# CLIPPER_CLAMPER_PCB.net
KiCad netlist of a schematic drawn in EasyEDA
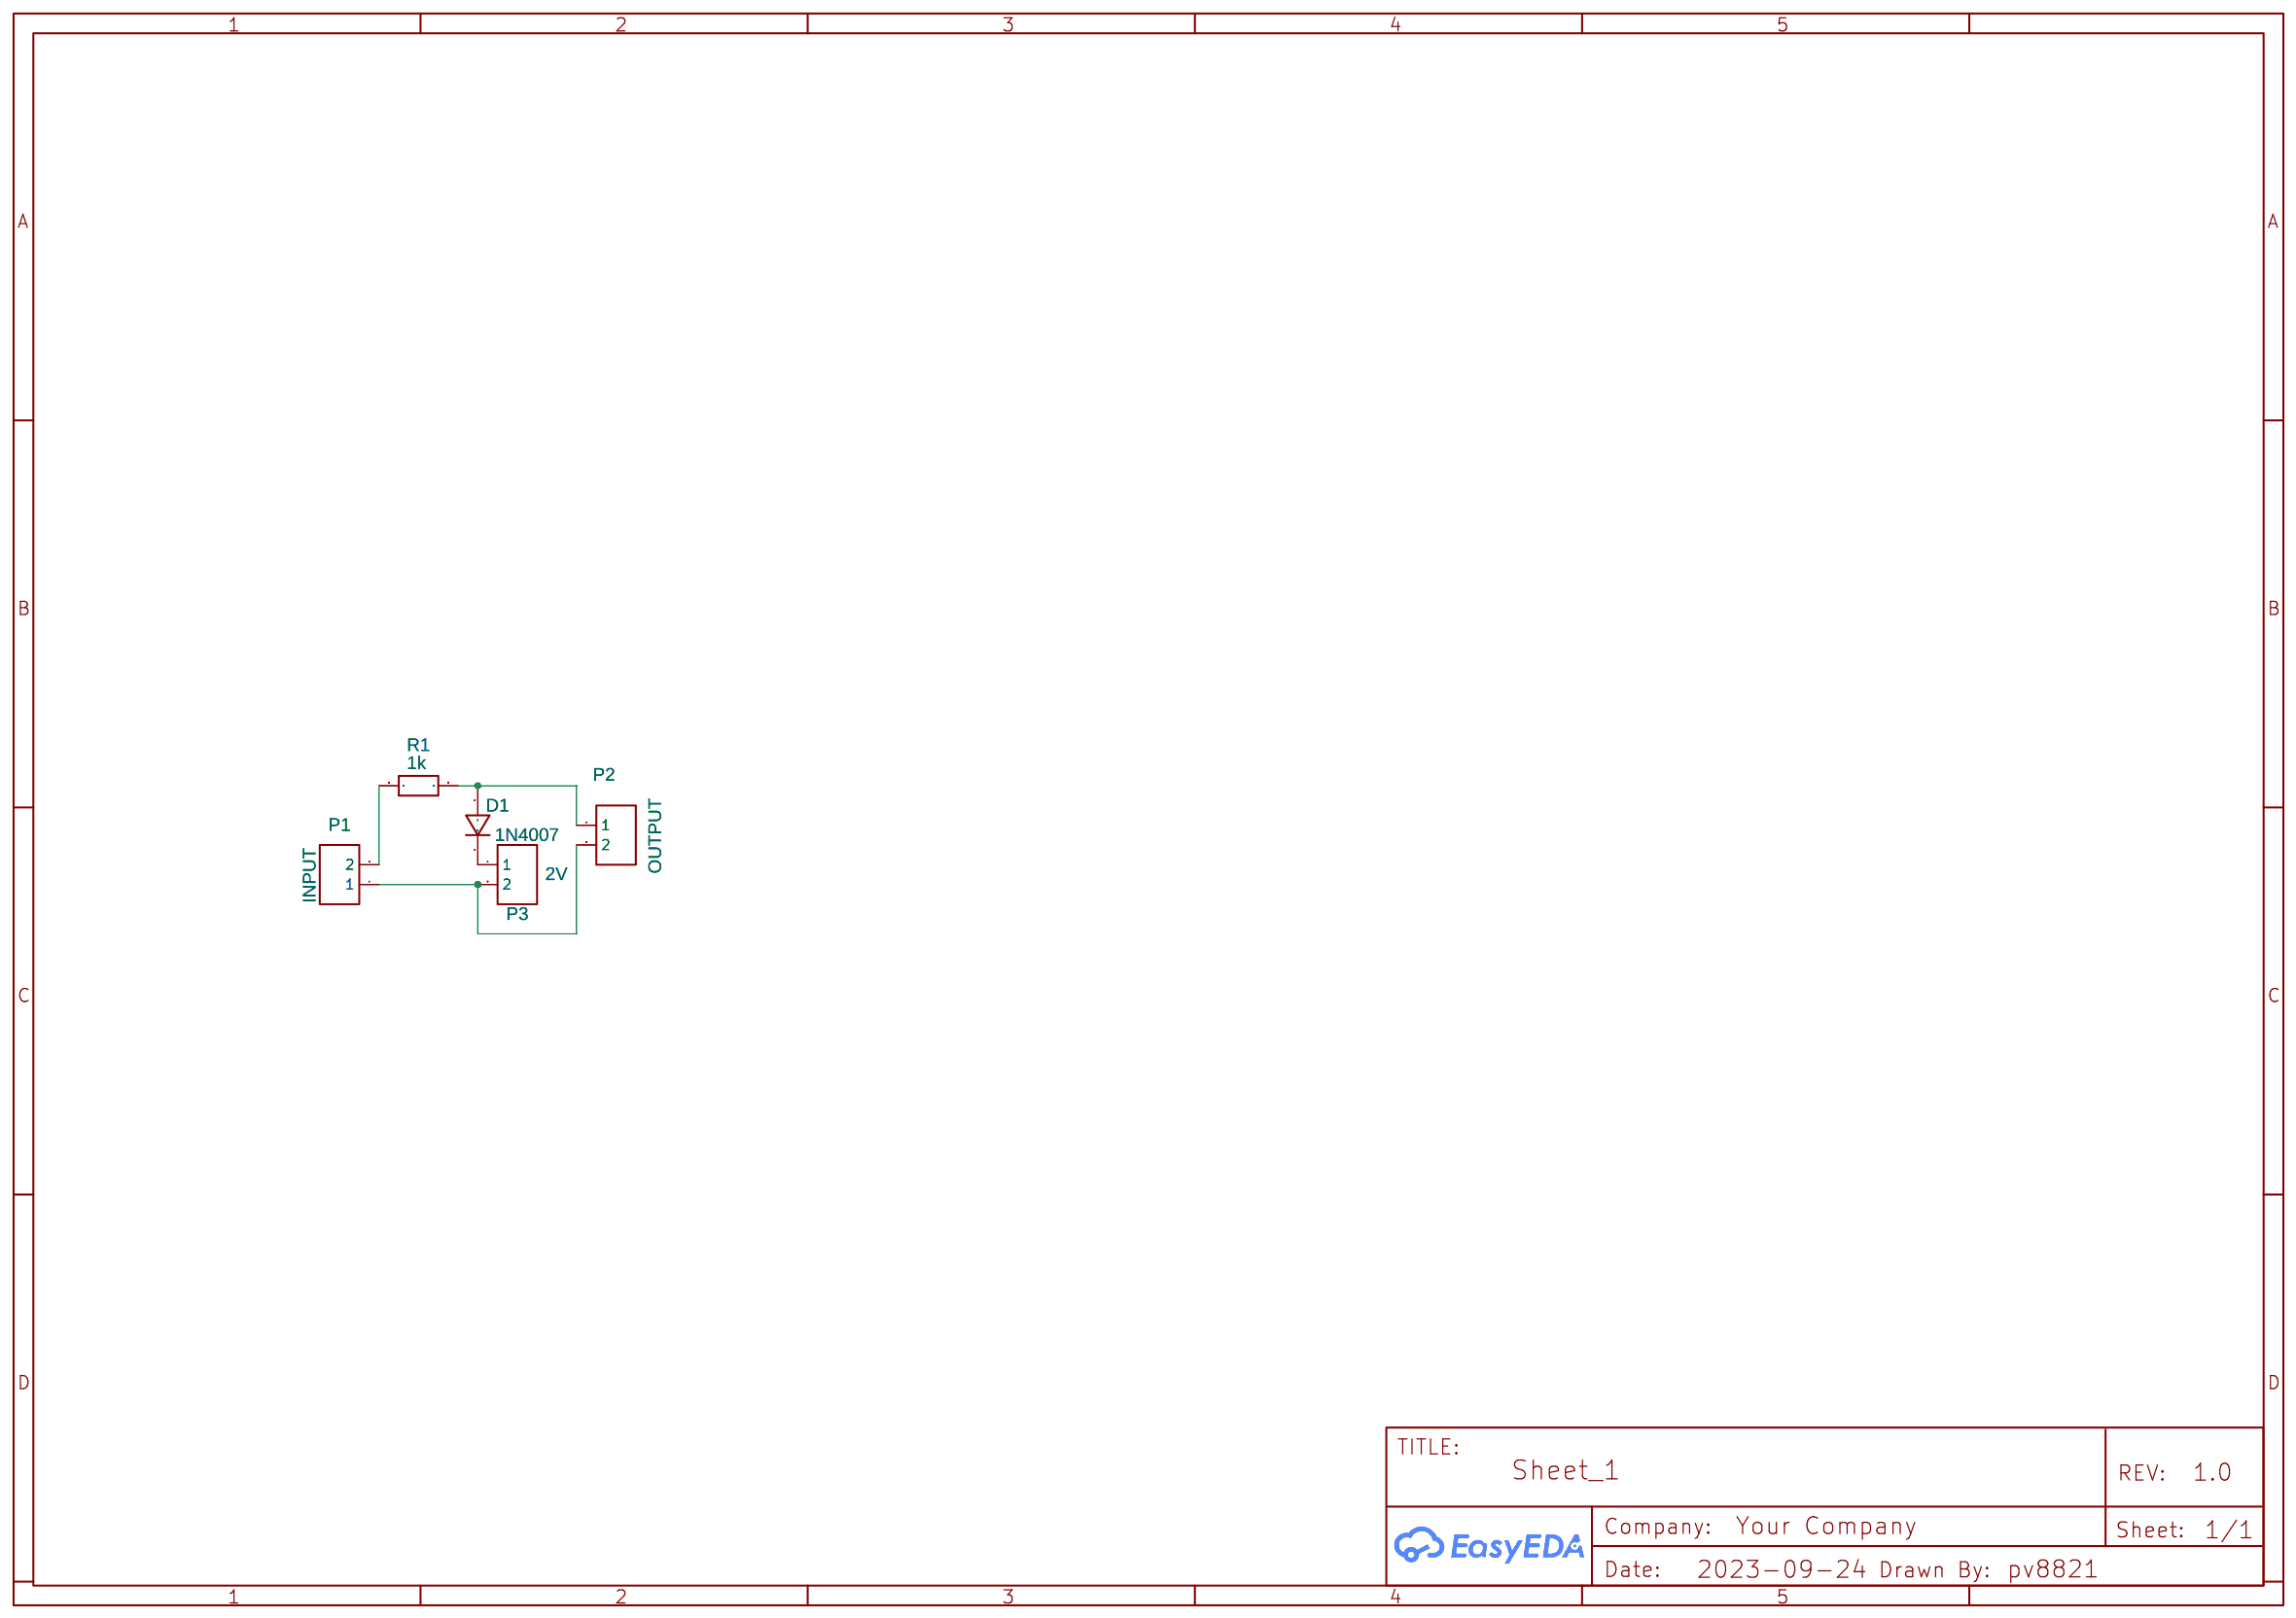
[diagram p0: schematic sheet]

(export (version "E")
  (design (tool "Eeschema 10.0.6"))
  (components
    (comp (ref "D1")
      (value "1N4007")
      (fields (field (name "Manufacturer") "SEMTECH"))
      (libsource (lib "") (part "1N4007"))
    )
    (comp (ref "P1") (value "INPUT") (libsource (lib "") (part "CONN-TH_2P-P5.00_1")))
    (comp (ref "P2") (value "OUTPUT") (libsource (lib "") (part "CONN-TH_2P-P5.00")))
    (comp (ref "P3") (value "2V") (libsource (lib "") (part "CONN-TH_2P-P5.00")))
    (comp (ref "R1") (value "1k") (libsource (lib "") (part "R_AXIAL-0.5_EU")))
  )
  (nets
    (net (code "1") (name "Net-(D1-Pad1)") (class "Default")
      (node (ref "D1") (pin "1") (pinfunction "1_1") (pintype "unspecified"))
      (node (ref "P3") (pin "1") (pinfunction "1_1") (pintype "unspecified"))
    )
    (net (code "2") (name "Net-(D1-Pad2)") (class "Default")
      (node (ref "D1") (pin "2") (pinfunction "2_2") (pintype "unspecified"))
      (node (ref "P2") (pin "1") (pinfunction "1_1") (pintype "unspecified"))
      (node (ref "R1") (pin "2") (pinfunction "2_2") (pintype "unspecified"))
    )
    (net (code "3") (name "Net-(P1-Pad1)") (class "Default")
      (node (ref "P1") (pin "1") (pinfunction "1_1") (pintype "unspecified"))
      (node (ref "P2") (pin "2") (pinfunction "2_2") (pintype "unspecified"))
      (node (ref "P3") (pin "2") (pinfunction "2_2") (pintype "unspecified"))
    )
    (net (code "4") (name "Net-(P1-Pad2)") (class "Default")
      (node (ref "P1") (pin "2") (pinfunction "2_2") (pintype "unspecified"))
      (node (ref "R1") (pin "1") (pinfunction "1_1") (pintype "unspecified"))
    )
  )
)
